# CP2102.net
KiCad netlist of a schematic drawn in Altium Designer
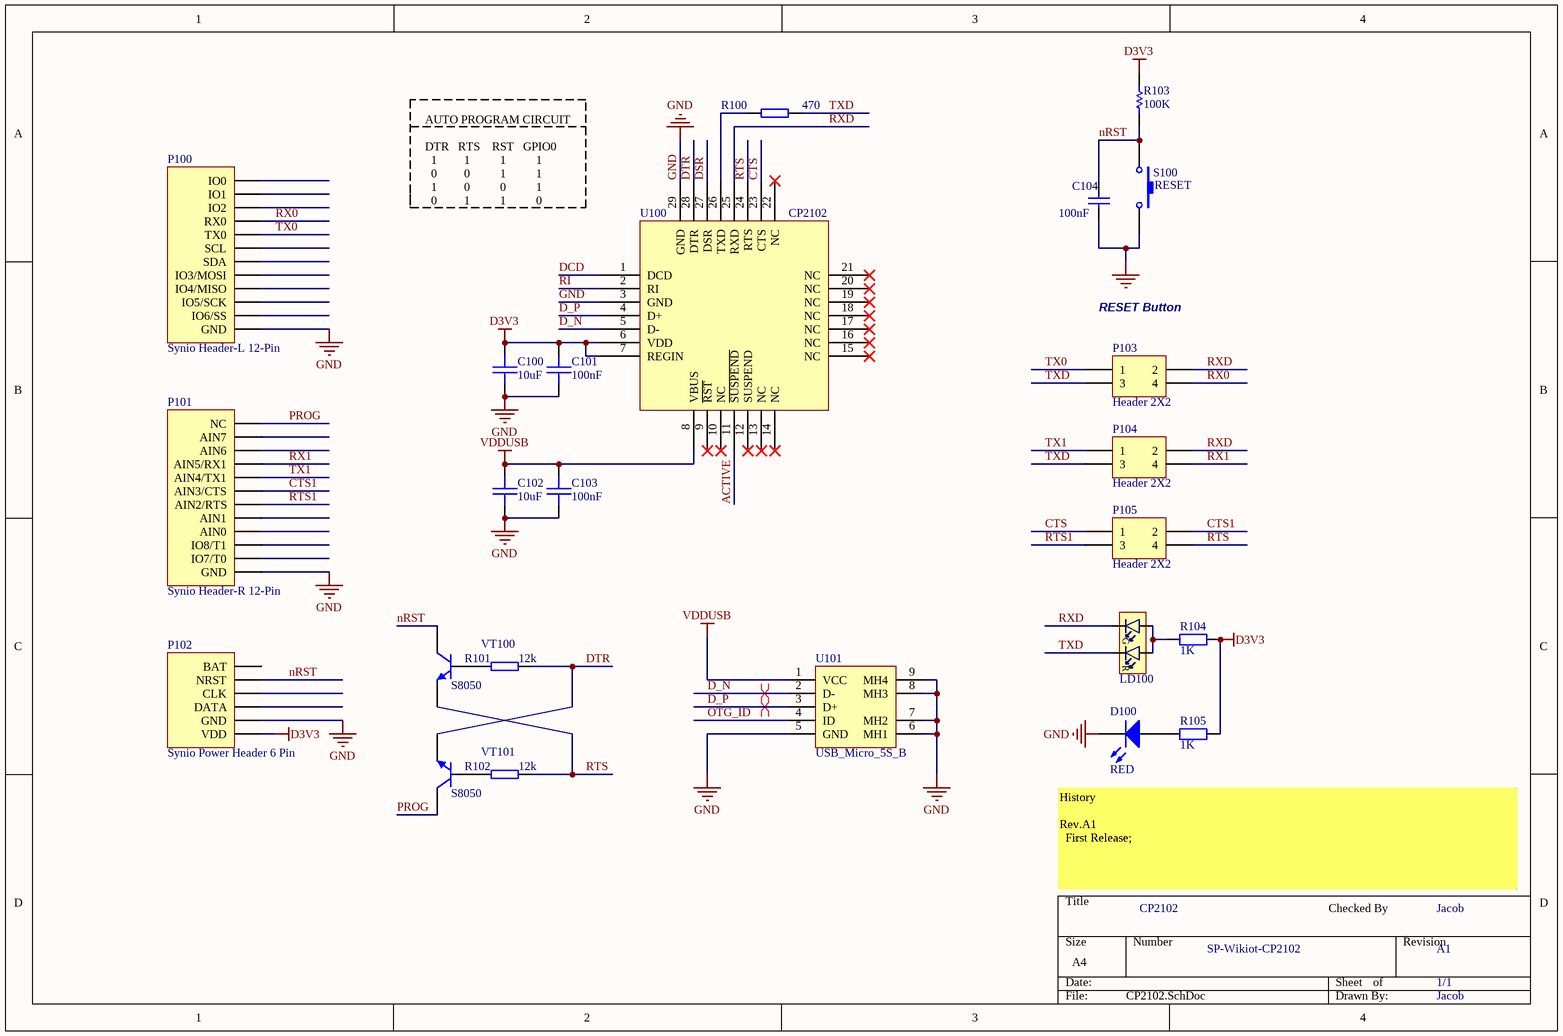
[diagram p0: CP2102.SchDoc]

(export (version "E")
  (design (tool "Eeschema 10.0.6"))
  (components
    (comp (ref "C100")
      (value "10uF")
      (footprint "C0603L")
      (description "Surface mount capacitor 0402")
      (libsource (lib "Vowstar_Basic_Device") (part "SMT_C_0402"))
    )
    (comp (ref "C101")
      (value "100nF")
      (footprint "C0603L")
      (description "Surface mount capacitor 0402")
      (libsource (lib "Vowstar_Basic_Device") (part "SMT_C_0402"))
    )
    (comp (ref "C102")
      (value "10uF")
      (footprint "C0603L")
      (description "Surface mount capacitor 0402")
      (libsource (lib "Vowstar_Basic_Device") (part "SMT_C_0402"))
    )
    (comp (ref "C103")
      (value "100nF")
      (footprint "C0603L")
      (description "Surface mount capacitor 0402")
      (libsource (lib "Vowstar_Basic_Device") (part "SMT_C_0402"))
    )
    (comp (ref "C104")
      (value "100nF")
      (footprint "0603M")
      (description "Capacitor")
      (fields (field (name "PUBLISHER") "Altium Limited"))
      (libsource (lib "Miscellaneous Devices") (part "CAP"))
    )
    (comp (ref "D100")
      (value "RED")
      (footprint "SMT_LED_0603")
      (description "Typical INFRARED GaAs LED")
      (fields (field (name "PUBLISHER") "Altium Limited"))
      (libsource (lib "Miscellaneous Devices") (part "LED0"))
    )
    (comp (ref "LD100")
      (value "LTST-C195KGJRKT")
      (footprint "0805-LED-Bi")
      (description "Avago, HSMF-A203 Bi-Color LED")
      (fields
        (field (name "MANUFACTURER") "Lite-On Inc")
        (field (name "2ND SOURCE PART NUMBER") "859-LTST-C195KGJRKT")
        (field (name "PUBLISHER") "Nordic Semiconductor")
      )
      (libsource (lib "Misc") (part "LED-DUAL"))
    )
    (comp (ref "P100")
      (value "Synio Header-L 12-Pin")
      (footprint "HDR1X12/2.54MM")
      (description "Synio Header-L, 12-Pin")
      (fields (field (name "PUBLISHER") "Altium Limited"))
      (libsource (lib "Connector") (part "Synio Header-L 12-Pin"))
    )
    (comp (ref "P101")
      (value "Synio Header-R 12-Pin")
      (footprint "HDR1X12/2.54MM")
      (description "Synio Header-R, 12-Pin")
      (fields (field (name "PUBLISHER") "Altium Limited"))
      (libsource (lib "Connector") (part "Synio Header-R 12-Pin"))
    )
    (comp (ref "P102")
      (value "Synio Power Header 6 Pin")
      (footprint "HDR1X6/2.54MM")
      (libsource (lib "Connector") (part "Synio Power Header 6 Pin"))
    )
    (comp (ref "P103")
      (value "Header 2X2")
      (footprint "HDR2X2/2.54MM")
      (description "Header, 2-Pin, Dual row")
      (fields (field (name "PUBLISHER") "Altium Limited"))
      (libsource (lib "Miscellaneous Connectors") (part "Header 2X2"))
    )
    (comp (ref "P104")
      (value "Header 2X2")
      (footprint "HDR2X2/2.54MM")
      (description "Header, 2-Pin, Dual row")
      (fields (field (name "PUBLISHER") "Altium Limited"))
      (libsource (lib "Miscellaneous Connectors") (part "Header 2X2"))
    )
    (comp (ref "P105")
      (value "Header 2X2")
      (footprint "HDR2X2/2.54MM")
      (description "Header, 2-Pin, Dual row")
      (fields (field (name "PUBLISHER") "Altium Limited"))
      (libsource (lib "Miscellaneous Connectors") (part "Header 2X2"))
    )
    (comp (ref "R100")
      (value "470")
      (footprint "R0603")
      (description "Surface mount resistor 0402")
      (libsource (lib "Vowstar_Basic_Device") (part "SMT_R_0402"))
    )
    (comp (ref "R101")
      (value "12k")
      (footprint "R0603")
      (description "Surface mount resistor 0402")
      (libsource (lib "Vowstar_Basic_Device") (part "SMT_R_0402"))
    )
    (comp (ref "R102")
      (value "12k")
      (footprint "R0603")
      (description "Surface mount resistor 0402")
      (libsource (lib "Vowstar_Basic_Device") (part "SMT_R_0402"))
    )
    (comp (ref "R103")
      (value "100K")
      (footprint "0603M")
      (description "Resistor")
      (fields (field (name "PUBLISHER") "Altium Limited"))
      (libsource (lib "Miscellaneous Devices") (part "res1"))
    )
    (comp (ref "R104")
      (value "1K")
      (footprint "0603M")
      (description "Resistor")
      (fields (field (name "PUBLISHER") "Altium Limited"))
      (libsource (lib "") (part "Res2_1"))
    )
    (comp (ref "R105")
      (value "1K")
      (footprint "0603M")
      (description "Resistor")
      (fields (field (name "PUBLISHER") "Altium Limited"))
      (libsource (lib "Miscellaneous Devices") (part "Res2"))
    )
    (comp (ref "S100")
      (value "RESET")
      (footprint "KEY-2x4-SMD")
      (description "Switch")
      (fields (field (name "PUBLISHER") "Altium Limited"))
      (libsource (lib "Miscellaneous Devices") (part "SW-PB"))
    )
    (comp (ref "U100")
      (value "CP2102")
      (footprint "QFN28")
      (libsource (lib "Vowstar_IC_General") (part "CP2102"))
    )
    (comp (ref "U101")
      (value "USB_Micro_5S_B")
      (footprint "USB_MICRO_5S_B")
      (description "USB micro female SMT with 4 fixed foot")
      (libsource (lib "Vowstar_Connector") (part "USB_Micro_5S_B"))
    )
    (comp (ref "VT100")
      (value "S8050")
      (footprint "SMT_TRIODE_NPN")
      (description "Surface mount NPN transistor, package SOT-23")
      (libsource (lib "Vowstar_Basic_Device") (part "SMT_TRIODE_NPN"))
    )
    (comp (ref "VT101")
      (value "S8050")
      (footprint "SMT_TRIODE_NPN")
      (description "Surface mount NPN transistor, package SOT-23")
      (libsource (lib "Vowstar_Basic_Device") (part "SMT_TRIODE_NPN"))
    )
  )
  (nets
    (net (code "1") (name "/ACTIVE") (class "Default")
      (node (ref "U100") (pin "11") (pinfunction "~{SUSPEND}_11") (pintype "passive"))
    )
    (net (code "2") (name "/CTS") (class "Default")
      (node (ref "P105") (pin "1") (pinfunction "1_1") (pintype "passive"))
      (node (ref "U100") (pin "23") (pinfunction "CTS_23") (pintype "passive"))
    )
    (net (code "3") (name "/CTS1") (class "Default")
      (node (ref "P101") (pin "7") (pinfunction "AIN3/CTS_7") (pintype "passive"))
      (node (ref "P105") (pin "2") (pinfunction "2_2") (pintype "passive"))
    )
    (net (code "4") (name "/DCD") (class "Default")
      (node (ref "U100") (pin "1") (pinfunction "DCD_1") (pintype "passive"))
    )
    (net (code "5") (name "/DSR") (class "Default")
      (node (ref "U100") (pin "27") (pinfunction "DSR_27") (pintype "passive"))
    )
    (net (code "6") (name "/DTR") (class "Default")
      (node (ref "R101") (pin "2") (pinfunction "2_2") (pintype "passive"))
      (node (ref "U100") (pin "28") (pinfunction "DTR_28") (pintype "passive"))
      (node (ref "VT101") (pin "2") (pinfunction "E_2") (pintype "passive"))
    )
    (net (code "7") (name "/D_N") (class "Default")
      (node (ref "U100") (pin "5") (pinfunction "D-_5") (pintype "passive"))
      (node (ref "U101") (pin "2") (pinfunction "D-_2") (pintype "passive"))
    )
    (net (code "8") (name "/D_P") (class "Default")
      (node (ref "U100") (pin "4") (pinfunction "D+_4") (pintype "passive"))
      (node (ref "U101") (pin "3") (pinfunction "D+_3") (pintype "passive"))
    )
    (net (code "9") (name "/OTG_ID") (class "Default")
      (node (ref "U101") (pin "4") (pinfunction "ID_4") (pintype "passive"))
    )
    (net (code "10") (name "/PROG") (class "Default")
      (node (ref "P101") (pin "12") (pinfunction "NC_12") (pintype "passive"))
      (node (ref "VT101") (pin "3") (pinfunction "C_3") (pintype "passive"))
    )
    (net (code "11") (name "/RI") (class "Default")
      (node (ref "U100") (pin "2") (pinfunction "RI_2") (pintype "passive"))
    )
    (net (code "12") (name "/RTS") (class "Default")
      (node (ref "P105") (pin "4") (pinfunction "4_4") (pintype "passive"))
      (node (ref "R102") (pin "2") (pinfunction "2_2") (pintype "passive"))
      (node (ref "U100") (pin "24") (pinfunction "RTS_24") (pintype "passive"))
      (node (ref "VT100") (pin "2") (pinfunction "E_2") (pintype "passive"))
    )
    (net (code "13") (name "/RTS1") (class "Default")
      (node (ref "P101") (pin "6") (pinfunction "AIN2/RTS_6") (pintype "passive"))
      (node (ref "P105") (pin "3") (pinfunction "3_3") (pintype "passive"))
    )
    (net (code "14") (name "/RX0") (class "Default")
      (node (ref "P100") (pin "9") (pinfunction "RX0_9") (pintype "passive"))
      (node (ref "P103") (pin "4") (pinfunction "4_4") (pintype "passive"))
    )
    (net (code "15") (name "/RX1") (class "Default")
      (node (ref "P101") (pin "9") (pinfunction "AIN5/RX1_9") (pintype "passive"))
      (node (ref "P104") (pin "4") (pinfunction "4_4") (pintype "passive"))
    )
    (net (code "16") (name "/RXD") (class "Default")
      (node (ref "LD100") (pin "1") (pinfunction "C1_1") (pintype "passive"))
      (node (ref "P103") (pin "2") (pinfunction "2_2") (pintype "passive"))
      (node (ref "P104") (pin "2") (pinfunction "2_2") (pintype "passive"))
      (node (ref "U100") (pin "25") (pinfunction "RXD_25") (pintype "passive"))
    )
    (net (code "17") (name "/TX0") (class "Default")
      (node (ref "P100") (pin "8") (pinfunction "TX0_8") (pintype "passive"))
      (node (ref "P103") (pin "1") (pinfunction "1_1") (pintype "passive"))
    )
    (net (code "18") (name "/TX1") (class "Default")
      (node (ref "P101") (pin "8") (pinfunction "AIN4/TX1_8") (pintype "passive"))
      (node (ref "P104") (pin "1") (pinfunction "1_1") (pintype "passive"))
    )
    (net (code "19") (name "/TXD") (class "Default")
      (node (ref "LD100") (pin "2") (pinfunction "C2_2") (pintype "passive"))
      (node (ref "P103") (pin "3") (pinfunction "3_3") (pintype "passive"))
      (node (ref "P104") (pin "3") (pinfunction "3_3") (pintype "passive"))
      (node (ref "R100") (pin "2") (pinfunction "2_2") (pintype "passive"))
    )
    (net (code "20") (name "/nRST") (class "Default")
      (node (ref "C104") (pin "2") (pinfunction "2_2") (pintype "passive"))
      (node (ref "P102") (pin "5") (pinfunction "NRST_5") (pintype "passive"))
      (node (ref "R103") (pin "1") (pinfunction "1_1") (pintype "passive"))
      (node (ref "S100") (pin "2") (pinfunction "2_2") (pintype "passive"))
      (node (ref "VT100") (pin "3") (pinfunction "C_3") (pintype "passive"))
    )
    (net (code "21") (name "D3V3") (class "Default")
      (node (ref "C100") (pin "1") (pinfunction "1_1") (pintype "passive"))
      (node (ref "C101") (pin "1") (pinfunction "1_1") (pintype "passive"))
      (node (ref "P102") (pin "1") (pinfunction "VDD_1") (pintype "passive"))
      (node (ref "R103") (pin "2") (pinfunction "2_2") (pintype "passive"))
      (node (ref "R104") (pin "1") (pinfunction "1_1") (pintype "passive"))
      (node (ref "R105") (pin "2") (pinfunction "2_2") (pintype "passive"))
      (node (ref "U100") (pin "6") (pinfunction "VDD_6") (pintype "passive"))
      (node (ref "U100") (pin "7") (pinfunction "REGIN_7") (pintype "passive"))
    )
    (net (code "22") (name "GND") (class "Default")
      (node (ref "C100") (pin "2") (pinfunction "2_2") (pintype "passive"))
      (node (ref "C101") (pin "2") (pinfunction "2_2") (pintype "passive"))
      (node (ref "C102") (pin "2") (pinfunction "2_2") (pintype "passive"))
      (node (ref "C103") (pin "2") (pinfunction "2_2") (pintype "passive"))
      (node (ref "C104") (pin "1") (pinfunction "1_1") (pintype "passive"))
      (node (ref "D100") (pin "2") (pinfunction "K_2") (pintype "passive"))
      (node (ref "P100") (pin "1") (pinfunction "GND_1") (pintype "passive"))
      (node (ref "P101") (pin "1") (pinfunction "GND_1") (pintype "passive"))
      (node (ref "P102") (pin "2") (pinfunction "GND_2") (pintype "passive"))
      (node (ref "S100") (pin "1") (pinfunction "1_1") (pintype "passive"))
      (node (ref "U100") (pin "29") (pinfunction "GND_29") (pintype "passive"))
      (node (ref "U100") (pin "3") (pinfunction "GND_3") (pintype "passive"))
      (node (ref "U101") (pin "5") (pinfunction "GND_5") (pintype "passive"))
      (node (ref "U101") (pin "6") (pinfunction "MH1_6") (pintype "passive"))
      (node (ref "U101") (pin "7") (pinfunction "MH2_7") (pintype "passive"))
      (node (ref "U101") (pin "8") (pinfunction "MH3_8") (pintype "passive"))
      (node (ref "U101") (pin "9") (pinfunction "MH4_9") (pintype "passive"))
    )
    (net (code "23") (name "Net-(D100-A)") (class "Default")
      (node (ref "D100") (pin "1") (pinfunction "A_1") (pintype "passive"))
      (node (ref "R105") (pin "1") (pinfunction "1_1") (pintype "passive"))
    )
    (net (code "24") (name "Net-(LD100-A1)") (class "Default")
      (node (ref "LD100") (pin "3") (pinfunction "A2_3") (pintype "passive"))
      (node (ref "LD100") (pin "4") (pinfunction "A1_4") (pintype "passive"))
      (node (ref "R104") (pin "2") (pinfunction "2_2") (pintype "passive"))
    )
    (net (code "25") (name "Net-(U100-TXD)") (class "Default")
      (node (ref "R100") (pin "1") (pinfunction "1_1") (pintype "passive"))
      (node (ref "U100") (pin "26") (pinfunction "TXD_26") (pintype "passive"))
    )
    (net (code "26") (name "Net-(VT100-B)") (class "Default")
      (node (ref "R101") (pin "1") (pinfunction "1_1") (pintype "passive"))
      (node (ref "VT100") (pin "1") (pinfunction "B_1") (pintype "passive"))
    )
    (net (code "27") (name "Net-(VT101-B)") (class "Default")
      (node (ref "R102") (pin "1") (pinfunction "1_1") (pintype "passive"))
      (node (ref "VT101") (pin "1") (pinfunction "B_1") (pintype "passive"))
    )
    (net (code "28") (name "VDDUSB") (class "Default")
      (node (ref "C102") (pin "1") (pinfunction "1_1") (pintype "passive"))
      (node (ref "C103") (pin "1") (pinfunction "1_1") (pintype "passive"))
      (node (ref "U100") (pin "8") (pinfunction "VBUS_8") (pintype "passive"))
      (node (ref "U101") (pin "1") (pinfunction "VCC_1") (pintype "passive"))
    )
    (net (code "29") (name "unconnected-(P100-IO0-Pad12)") (class "Default")
      (node (ref "P100") (pin "12") (pinfunction "IO0_12") (pintype "passive"))
    )
    (net (code "30") (name "unconnected-(P100-IO1-Pad11)") (class "Default")
      (node (ref "P100") (pin "11") (pinfunction "IO1_11") (pintype "passive"))
    )
    (net (code "31") (name "unconnected-(P100-IO2-Pad10)") (class "Default")
      (node (ref "P100") (pin "10") (pinfunction "IO2_10") (pintype "passive"))
    )
    (net (code "32") (name "unconnected-(P100-IO3{slash}MOSI-Pad5)") (class "Default")
      (node (ref "P100") (pin "5") (pinfunction "IO3/MOSI_5") (pintype "passive"))
    )
    (net (code "33") (name "unconnected-(P100-IO4{slash}MISO-Pad4)") (class "Default")
      (node (ref "P100") (pin "4") (pinfunction "IO4/MISO_4") (pintype "passive"))
    )
    (net (code "34") (name "unconnected-(P100-IO5{slash}SCK-Pad3)") (class "Default")
      (node (ref "P100") (pin "3") (pinfunction "IO5/SCK_3") (pintype "passive"))
    )
    (net (code "35") (name "unconnected-(P100-IO6{slash}SS-Pad2)") (class "Default")
      (node (ref "P100") (pin "2") (pinfunction "IO6/SS_2") (pintype "passive"))
    )
    (net (code "36") (name "unconnected-(P100-SCL-Pad7)") (class "Default")
      (node (ref "P100") (pin "7") (pinfunction "SCL_7") (pintype "passive"))
    )
    (net (code "37") (name "unconnected-(P100-SDA-Pad6)") (class "Default")
      (node (ref "P100") (pin "6") (pinfunction "SDA_6") (pintype "passive"))
    )
    (net (code "38") (name "unconnected-(P101-AIN0-Pad4)") (class "Default")
      (node (ref "P101") (pin "4") (pinfunction "AIN0_4") (pintype "passive"))
    )
    (net (code "39") (name "unconnected-(P101-AIN1-Pad5)") (class "Default")
      (node (ref "P101") (pin "5") (pinfunction "AIN1_5") (pintype "passive"))
    )
    (net (code "40") (name "unconnected-(P101-AIN6-Pad10)") (class "Default")
      (node (ref "P101") (pin "10") (pinfunction "AIN6_10") (pintype "passive"))
    )
    (net (code "41") (name "unconnected-(P101-AIN7-Pad11)") (class "Default")
      (node (ref "P101") (pin "11") (pinfunction "AIN7_11") (pintype "passive"))
    )
    (net (code "42") (name "unconnected-(P101-IO7{slash}T0-Pad2)") (class "Default")
      (node (ref "P101") (pin "2") (pinfunction "IO7/T0_2") (pintype "passive"))
    )
    (net (code "43") (name "unconnected-(P101-IO8{slash}T1-Pad3)") (class "Default")
      (node (ref "P101") (pin "3") (pinfunction "IO8/T1_3") (pintype "passive"))
    )
    (net (code "44") (name "unconnected-(P102-BAT-Pad6)") (class "Default")
      (node (ref "P102") (pin "6") (pinfunction "BAT_6") (pintype "passive"))
    )
    (net (code "45") (name "unconnected-(P102-CLK-Pad4)") (class "Default")
      (node (ref "P102") (pin "4") (pinfunction "CLK_4") (pintype "passive"))
    )
    (net (code "46") (name "unconnected-(P102-DATA-Pad3)") (class "Default")
      (node (ref "P102") (pin "3") (pinfunction "DATA_3") (pintype "passive"))
    )
    (net (code "47") (name "unconnected-(U100-NC-Pad10)") (class "Default")
      (node (ref "U100") (pin "10") (pinfunction "NC_10") (pintype "passive+no_connect"))
    )
    (net (code "48") (name "unconnected-(U100-NC-Pad13)") (class "Default")
      (node (ref "U100") (pin "13") (pinfunction "NC_13") (pintype "passive+no_connect"))
    )
    (net (code "49") (name "unconnected-(U100-NC-Pad14)") (class "Default")
      (node (ref "U100") (pin "14") (pinfunction "NC_14") (pintype "passive+no_connect"))
    )
    (net (code "50") (name "unconnected-(U100-NC-Pad15)") (class "Default")
      (node (ref "U100") (pin "15") (pinfunction "NC_15") (pintype "passive+no_connect"))
    )
    (net (code "51") (name "unconnected-(U100-NC-Pad16)") (class "Default")
      (node (ref "U100") (pin "16") (pinfunction "NC_16") (pintype "passive+no_connect"))
    )
    (net (code "52") (name "unconnected-(U100-NC-Pad17)") (class "Default")
      (node (ref "U100") (pin "17") (pinfunction "NC_17") (pintype "passive+no_connect"))
    )
    (net (code "53") (name "unconnected-(U100-NC-Pad18)") (class "Default")
      (node (ref "U100") (pin "18") (pinfunction "NC_18") (pintype "passive+no_connect"))
    )
    (net (code "54") (name "unconnected-(U100-NC-Pad19)") (class "Default")
      (node (ref "U100") (pin "19") (pinfunction "NC_19") (pintype "passive+no_connect"))
    )
    (net (code "55") (name "unconnected-(U100-NC-Pad20)") (class "Default")
      (node (ref "U100") (pin "20") (pinfunction "NC_20") (pintype "passive+no_connect"))
    )
    (net (code "56") (name "unconnected-(U100-NC-Pad21)") (class "Default")
      (node (ref "U100") (pin "21") (pinfunction "NC_21") (pintype "passive+no_connect"))
    )
    (net (code "57") (name "unconnected-(U100-NC-Pad22)") (class "Default")
      (node (ref "U100") (pin "22") (pinfunction "NC_22") (pintype "passive+no_connect"))
    )
    (net (code "58") (name "unconnected-(U100-SUSPEND-Pad12)") (class "Default")
      (node (ref "U100") (pin "12") (pinfunction "SUSPEND_12") (pintype "passive+no_connect"))
    )
    (net (code "59") (name "unconnected-(U100-~{RST}-Pad9)") (class "Default")
      (node (ref "U100") (pin "9") (pinfunction "~{RST}_9") (pintype "passive+no_connect"))
    )
  )
)
